# MSP430G2553.net
KiCad netlist of a schematic drawn in Altium Designer
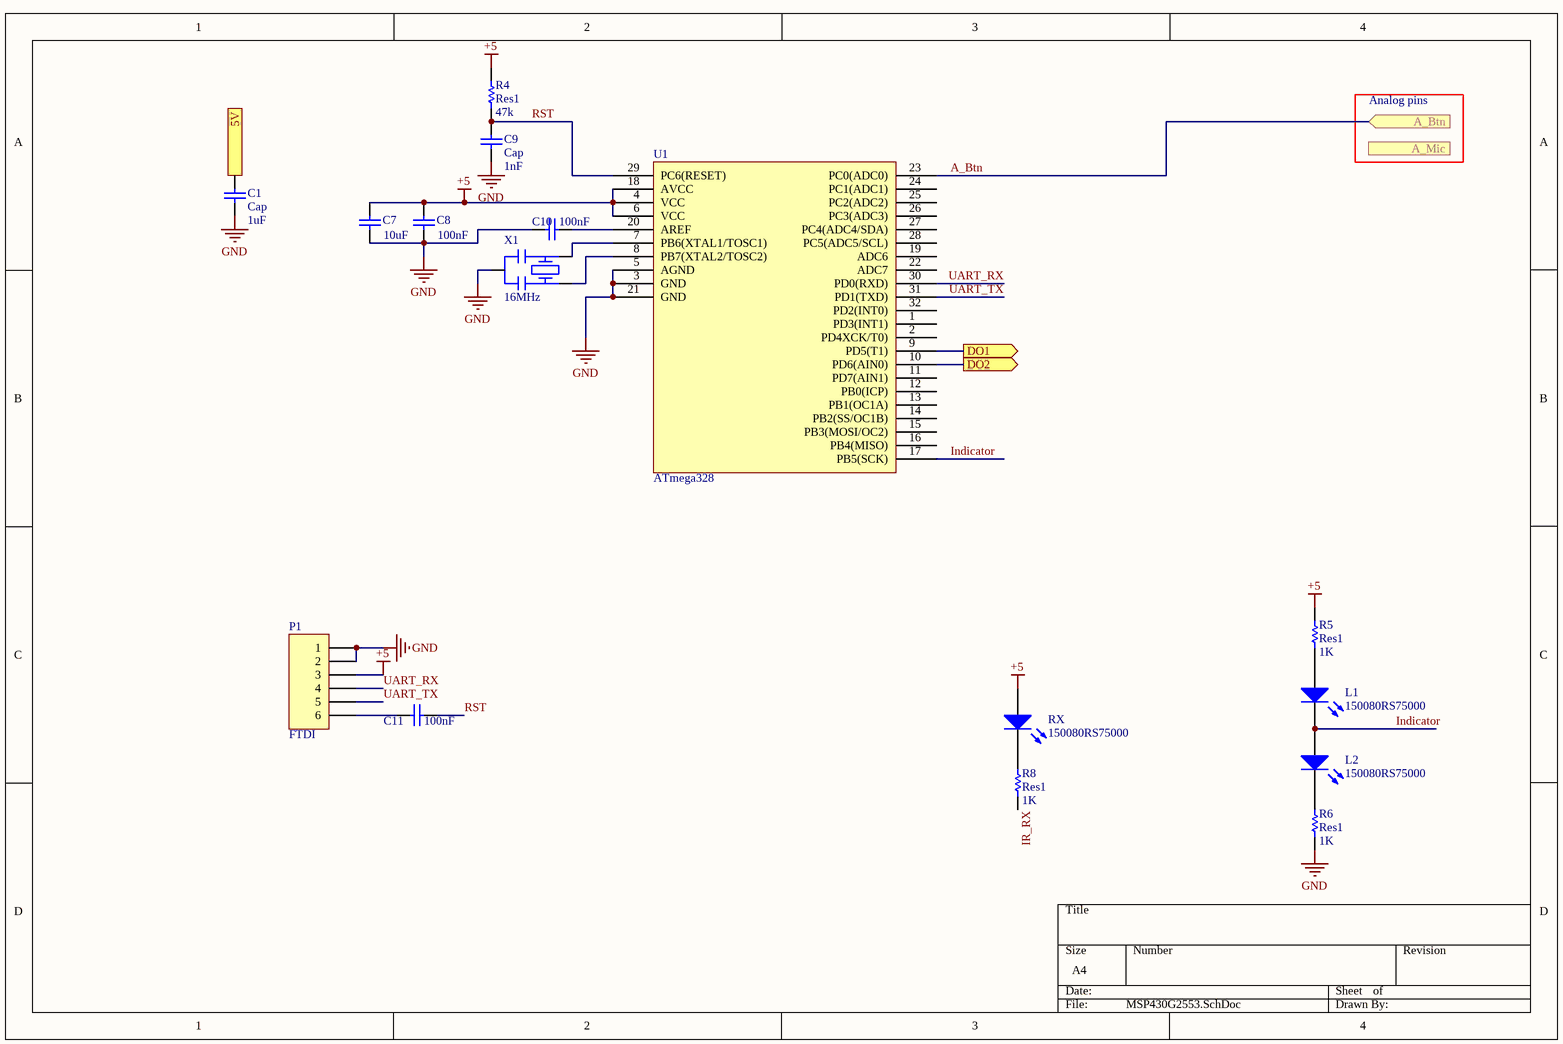
[diagram p0: MSP430G2553.SchDoc]

(export (version "E")
  (design (tool "Eeschema 10.0.6"))
  (components
    (comp (ref "C1")
      (value "Cap")
      (footprint "6-0805_M")
      (description "Capacitor")
      (fields (field (name "ALTIUM_VALUE") "1uF") (field (name "PUBLISHER") "Altium Limited"))
      (libsource (lib "Miscellaneous Devices") (part "Cap"))
    )
    (comp (ref "C7")
      (value "10uF")
      (footprint "6-0805_N")
      (description "Capacitor")
      (fields (field (name "Comment") "Cap") (field (name "PUBLISHER") "Altium Limited"))
      (libsource (lib "Miscellaneous Devices") (part "Cap"))
    )
    (comp (ref "C8")
      (value "100nF")
      (footprint "6-0805_N")
      (description "Capacitor")
      (fields (field (name "Comment") "Cap") (field (name "PUBLISHER") "Altium Limited"))
      (libsource (lib "Miscellaneous Devices") (part "Cap"))
    )
    (comp (ref "C9")
      (value "Cap")
      (footprint "6-0805_N")
      (description "Capacitor")
      (fields (field (name "ALTIUM_VALUE") "1nF") (field (name "PUBLISHER") "Altium Limited"))
      (libsource (lib "Miscellaneous Devices") (part "Cap"))
    )
    (comp (ref "C10")
      (value "100nF")
      (footprint "6-0805_N")
      (description "Capacitor")
      (fields (field (name "Comment") "Cap") (field (name "PUBLISHER") "Altium Limited"))
      (libsource (lib "Miscellaneous Devices") (part "Cap"))
    )
    (comp (ref "C11")
      (value "100nF")
      (footprint "6-0805_N")
      (description "Capacitor")
      (fields (field (name "Comment") "Cap") (field (name "PUBLISHER") "Altium Limited"))
      (libsource (lib "Miscellaneous Devices") (part "Cap"))
    )
    (comp (ref "L1")
      (value "150080RS75000")
      (footprint "0805_A")
      (description "SMD mono-color Chip LED, WL-SMCW, Red")
      (libsource (lib "WL-SMCW SMD chip LED top view mono-color waterclear") (part "150080RS75000"))
    )
    (comp (ref "L2")
      (value "150080RS75000")
      (footprint "0805_A")
      (description "SMD mono-color Chip LED, WL-SMCW, Red")
      (libsource (lib "WL-SMCW SMD chip LED top view mono-color waterclear") (part "150080RS75000"))
    )
    (comp (ref "P1")
      (value "FTDI")
      (footprint "HDR1X6H")
      (description "Header, 6-Pin, Right Angle")
      (fields (field (name "PUBLISHER") "Altium Limited"))
      (libsource (lib "Miscellaneous Connectors") (part "Header 6H"))
    )
    (comp (ref "R4")
      (value "Res1")
      (footprint "6-0805_N")
      (description "Resistor")
      (fields (field (name "ALTIUM_VALUE") "47k") (field (name "PUBLISHER") "Altium Limited"))
      (libsource (lib "Miscellaneous Devices") (part "Res1"))
    )
    (comp (ref "R5")
      (value "Res1")
      (footprint "6-0805_M")
      (description "Resistor")
      (fields (field (name "ALTIUM_VALUE") "1K") (field (name "PUBLISHER") "Altium Limited"))
      (libsource (lib "Miscellaneous Devices") (part "Res1"))
    )
    (comp (ref "R6")
      (value "Res1")
      (footprint "6-0805_M")
      (description "Resistor")
      (fields (field (name "ALTIUM_VALUE") "1K") (field (name "PUBLISHER") "Altium Limited"))
      (libsource (lib "Miscellaneous Devices") (part "Res1"))
    )
    (comp (ref "R8")
      (value "Res1")
      (footprint "6-0805_N")
      (description "Resistor")
      (fields (field (name "ALTIUM_VALUE") "1K") (field (name "PUBLISHER") "Altium Limited"))
      (libsource (lib "Miscellaneous Devices") (part "Res1"))
    )
    (comp (ref "RX")
      (value "150080RS75000")
      (footprint "0805_A")
      (description "SMD mono-color Chip LED, WL-SMCW, Red")
      (libsource (lib "WL-SMCW SMD chip LED top view mono-color waterclear") (part "150080RS75000"))
    )
    (comp (ref "U1") (value "ATmega328") (footprint "TQFP32") (libsource (lib "blandat") (part "ATmega328")))
    (comp (ref "X1")
      (value "16MHz")
      (footprint "osc")
      (description "CSTCE16M0V53-R0")
      (libsource (lib "blandat") (part "xtal_1"))
    )
  )
  (nets
    (net (code "1") (name "+5") (class "Default")
      (node (ref "C7") (pin "1") (pinfunction "1_1") (pintype "passive"))
      (node (ref "C8") (pin "1") (pinfunction "1_1") (pintype "passive"))
      (node (ref "P1") (pin "3") (pinfunction "3_3") (pintype "passive"))
      (node (ref "R4") (pin "2") (pinfunction "2_2") (pintype "passive"))
      (node (ref "R5") (pin "2") (pinfunction "2_2") (pintype "passive"))
      (node (ref "RX") (pin "2") (pinfunction "A_2") (pintype "passive"))
      (node (ref "U1") (pin "18") (pinfunction "AVCC_18") (pintype "passive"))
      (node (ref "U1") (pin "4") (pinfunction "VCC_4") (pintype "passive"))
      (node (ref "U1") (pin "6") (pinfunction "VCC_6") (pintype "passive"))
    )
    (net (code "2") (name "/5V") (class "Default")
      (node (ref "C1") (pin "1") (pinfunction "1_1") (pintype "passive"))
    )
    (net (code "3") (name "/A_Btn") (class "Default")
      (node (ref "U1") (pin "23") (pinfunction "PC0(ADC0)_23") (pintype "passive"))
    )
    (net (code "5") (name "/DO1") (class "Default")
      (node (ref "U1") (pin "9") (pinfunction "PD5(T1)_9") (pintype "passive"))
    )
    (net (code "6") (name "/DO2") (class "Default")
      (node (ref "U1") (pin "10") (pinfunction "PD6(AIN0)_10") (pintype "passive"))
    )
    (net (code "7") (name "/IR_RX") (class "Default")
      (node (ref "R8") (pin "1") (pinfunction "1_1") (pintype "passive"))
    )
    (net (code "8") (name "/Indicator") (class "Default")
      (node (ref "L1") (pin "1") (pinfunction "K_1") (pintype "passive"))
      (node (ref "L2") (pin "2") (pinfunction "A_2") (pintype "passive"))
      (node (ref "U1") (pin "17") (pinfunction "PB5(SCK)_17") (pintype "passive"))
    )
    (net (code "9") (name "/RST") (class "Default")
      (node (ref "C11") (pin "1") (pinfunction "1_1") (pintype "passive"))
      (node (ref "C9") (pin "2") (pinfunction "2_2") (pintype "passive"))
      (node (ref "R4") (pin "1") (pinfunction "1_1") (pintype "passive"))
      (node (ref "U1") (pin "29") (pinfunction "PC6(RESET)_29") (pintype "passive"))
    )
    (net (code "10") (name "/UART_RX") (class "Default")
      (node (ref "P1") (pin "4") (pinfunction "4_4") (pintype "passive"))
      (node (ref "U1") (pin "30") (pinfunction "PD0(RXD)_30") (pintype "passive"))
    )
    (net (code "11") (name "/UART_TX") (class "Default")
      (node (ref "P1") (pin "5") (pinfunction "5_5") (pintype "passive"))
      (node (ref "U1") (pin "31") (pinfunction "PD1(TXD)_31") (pintype "passive"))
    )
    (net (code "12") (name "GND") (class "Default")
      (node (ref "C1") (pin "2") (pinfunction "2_2") (pintype "passive"))
      (node (ref "C10") (pin "2") (pinfunction "2_2") (pintype "passive"))
      (node (ref "C7") (pin "2") (pinfunction "2_2") (pintype "passive"))
      (node (ref "C8") (pin "2") (pinfunction "2_2") (pintype "passive"))
      (node (ref "C9") (pin "1") (pinfunction "1_1") (pintype "passive"))
      (node (ref "P1") (pin "1") (pinfunction "1_1") (pintype "passive"))
      (node (ref "P1") (pin "2") (pinfunction "2_2") (pintype "passive"))
      (node (ref "R6") (pin "1") (pinfunction "1_1") (pintype "passive"))
      (node (ref "U1") (pin "21") (pinfunction "GND_21") (pintype "passive"))
      (node (ref "U1") (pin "3") (pinfunction "GND_3") (pintype "passive"))
      (node (ref "U1") (pin "5") (pinfunction "AGND_5") (pintype "passive"))
      (node (ref "X1") (pin "GND") (pinfunction "GND_GND") (pintype "passive"))
    )
    (net (code "13") (name "Net-(C11-Pad2)") (class "Default")
      (node (ref "C11") (pin "2") (pinfunction "2_2") (pintype "passive"))
      (node (ref "P1") (pin "6") (pinfunction "6_6") (pintype "passive"))
    )
    (net (code "14") (name "Net-(L1-A)") (class "Default")
      (node (ref "L1") (pin "2") (pinfunction "A_2") (pintype "passive"))
      (node (ref "R5") (pin "1") (pinfunction "1_1") (pintype "passive"))
    )
    (net (code "15") (name "Net-(L2-K)") (class "Default")
      (node (ref "L2") (pin "1") (pinfunction "K_1") (pintype "passive"))
      (node (ref "R6") (pin "2") (pinfunction "2_2") (pintype "passive"))
    )
    (net (code "16") (name "Net-(RX-K)") (class "Default")
      (node (ref "R8") (pin "2") (pinfunction "2_2") (pintype "passive"))
      (node (ref "RX") (pin "1") (pinfunction "K_1") (pintype "passive"))
    )
    (net (code "17") (name "Net-(U1-AREF)") (class "Default")
      (node (ref "C10") (pin "1") (pinfunction "1_1") (pintype "passive"))
      (node (ref "U1") (pin "20") (pinfunction "AREF_20") (pintype "passive"))
    )
    (net (code "18") (name "Net-(U1-PB6(XTAL1{slash}TOSC1))") (class "Default")
      (node (ref "U1") (pin "7") (pinfunction "PB6(XTAL1/TOSC1)_7") (pintype "passive"))
      (node (ref "X1") (pin "OSCO") (pinfunction "OSCO_OSCO") (pintype "passive"))
    )
    (net (code "19") (name "Net-(U1-PB7(XTAL2{slash}TOSC2))") (class "Default")
      (node (ref "U1") (pin "8") (pinfunction "PB7(XTAL2/TOSC2)_8") (pintype "passive"))
      (node (ref "X1") (pin "OSCI") (pinfunction "OSCI_OSCI") (pintype "passive"))
    )
    (net (code "20") (name "unconnected-(U1-ADC6-Pad19)") (class "Default")
      (node (ref "U1") (pin "19") (pinfunction "ADC6_19") (pintype "passive"))
    )
    (net (code "21") (name "unconnected-(U1-ADC7-Pad22)") (class "Default")
      (node (ref "U1") (pin "22") (pinfunction "ADC7_22") (pintype "passive"))
    )
    (net (code "22") (name "unconnected-(U1-PB0(ICP)-Pad12)") (class "Default")
      (node (ref "U1") (pin "12") (pinfunction "PB0(ICP)_12") (pintype "passive"))
    )
    (net (code "23") (name "unconnected-(U1-PB1(OC1A)-Pad13)") (class "Default")
      (node (ref "U1") (pin "13") (pinfunction "PB1(OC1A)_13") (pintype "passive"))
    )
    (net (code "24") (name "unconnected-(U1-PB2(SS{slash}OC1B)-Pad14)") (class "Default")
      (node (ref "U1") (pin "14") (pinfunction "PB2(SS/OC1B)_14") (pintype "passive"))
    )
    (net (code "25") (name "unconnected-(U1-PB3(MOSI{slash}OC2)-Pad15)") (class "Default")
      (node (ref "U1") (pin "15") (pinfunction "PB3(MOSI/OC2)_15") (pintype "passive"))
    )
    (net (code "26") (name "unconnected-(U1-PB4(MISO)-Pad16)") (class "Default")
      (node (ref "U1") (pin "16") (pinfunction "PB4(MISO)_16") (pintype "passive"))
    )
    (net (code "27") (name "unconnected-(U1-PC1(ADC1)-Pad24)") (class "Default")
      (node (ref "U1") (pin "24") (pinfunction "PC1(ADC1)_24") (pintype "passive"))
    )
    (net (code "28") (name "unconnected-(U1-PC2(ADC2)-Pad25)") (class "Default")
      (node (ref "U1") (pin "25") (pinfunction "PC2(ADC2)_25") (pintype "passive"))
    )
    (net (code "29") (name "unconnected-(U1-PC3(ADC3)-Pad26)") (class "Default")
      (node (ref "U1") (pin "26") (pinfunction "PC3(ADC3)_26") (pintype "passive"))
    )
    (net (code "30") (name "unconnected-(U1-PC4(ADC4{slash}SDA)-Pad27)") (class "Default")
      (node (ref "U1") (pin "27") (pinfunction "PC4(ADC4/SDA)_27") (pintype "passive"))
    )
    (net (code "31") (name "unconnected-(U1-PC5(ADC5{slash}SCL)-Pad28)") (class "Default")
      (node (ref "U1") (pin "28") (pinfunction "PC5(ADC5/SCL)_28") (pintype "passive"))
    )
    (net (code "32") (name "unconnected-(U1-PD2(INT0)-Pad32)") (class "Default")
      (node (ref "U1") (pin "32") (pinfunction "PD2(INT0)_32") (pintype "passive"))
    )
    (net (code "33") (name "unconnected-(U1-PD3(INT1)-Pad1)") (class "Default")
      (node (ref "U1") (pin "1") (pinfunction "PD3(INT1)_1") (pintype "passive"))
    )
    (net (code "34") (name "unconnected-(U1-PD4XCK{slash}T0)-Pad2)") (class "Default")
      (node (ref "U1") (pin "2") (pinfunction "PD4XCK/T0)_2") (pintype "passive"))
    )
    (net (code "35") (name "unconnected-(U1-PD7(AIN1)-Pad11)") (class "Default")
      (node (ref "U1") (pin "11") (pinfunction "PD7(AIN1)_11") (pintype "passive"))
    )
  )
)
